# CLOCK.net
KiCad netlist of a schematic drawn in Altium Designer
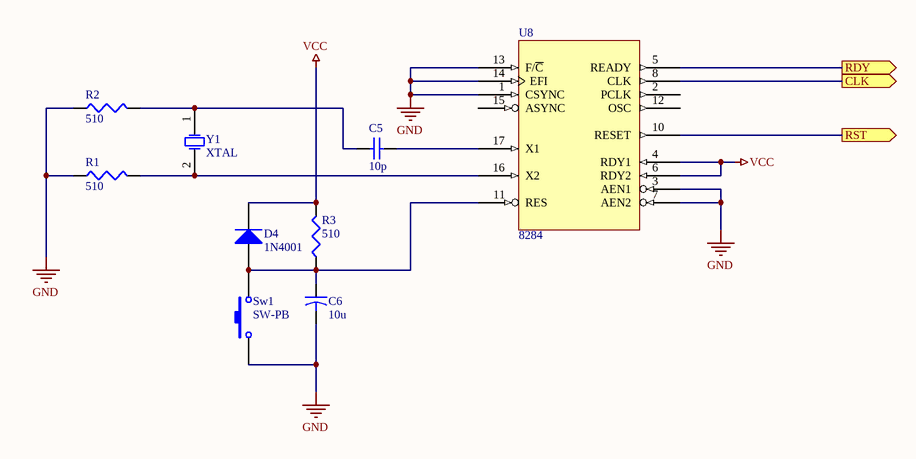
[diagram p0: CLOCK.SchDoc]

(export (version "E")
  (design (tool "Eeschema 10.0.6"))
  (components
    (comp (ref "C5")
      (value "10p")
      (footprint "RAD-0.3")
      (description "Capacitor")
      (fields (field (name "Comment") "Cap") (field (name "PUBLISHER") "Altium Limited"))
      (libsource (lib "8088") (part "Cap"))
    )
    (comp (ref "C6")
      (value "10u")
      (footprint "CAPR5-4X5")
      (description "Capacitor")
      (fields (field (name "Comment") "Cap2") (field (name "PUBLISHER") "Altium Limited"))
      (libsource (lib "8088") (part "Cap2"))
    )
    (comp (ref "D4")
      (value "1N4001")
      (footprint "DO-41")
      (description "1 Amp General Purpose Rectifier")
      (fields (field (name "PUBLISHER") "Altium Limited"))
      (libsource (lib "8088") (part "Diode 1N4001"))
    )
    (comp (ref "R1")
      (value "510")
      (footprint "J1-0603")
      (description "Resistor")
      (fields (field (name "Comment") "Res3") (field (name "PUBLISHER") "Altium Limited"))
      (libsource (lib "8088") (part "Res3"))
    )
    (comp (ref "R2")
      (value "510")
      (footprint "J1-0603")
      (description "Resistor")
      (fields (field (name "Comment") "Res3") (field (name "PUBLISHER") "Altium Limited"))
      (libsource (lib "8088") (part "Res3"))
    )
    (comp (ref "R3")
      (value "510")
      (footprint "J1-0603")
      (description "Resistor")
      (fields (field (name "Comment") "Res3") (field (name "PUBLISHER") "Altium Limited"))
      (libsource (lib "8088") (part "Res3"))
    )
    (comp (ref "Sw1")
      (value "SW-PB")
      (footprint "SPST-2")
      (description "Switch")
      (fields (field (name "PUBLISHER") "Altium Limited"))
      (libsource (lib "8088") (part "SW-PB"))
    )
    (comp (ref "U8") (value "8284") (footprint "DIP18") (libsource (lib "8088") (part "8284")))
    (comp (ref "Y1")
      (value "XTAL")
      (footprint "R38")
      (description "Crystal Oscillator")
      (fields (field (name "PUBLISHER") "Altium Limited"))
      (libsource (lib "8088") (part "XTAL"))
    )
  )
  (nets
    (net (code "1") (name "/CLK") (class "Default")
      (node (ref "U8") (pin "8") (pinfunction "CLK_8") (pintype "output"))
    )
    (net (code "2") (name "/RDY") (class "Default")
      (node (ref "U8") (pin "5") (pinfunction "READY_5") (pintype "output"))
    )
    (net (code "3") (name "/RST") (class "Default")
      (node (ref "U8") (pin "10") (pinfunction "RESET_10") (pintype "output"))
    )
    (net (code "4") (name "GND") (class "Default")
      (node (ref "C6") (pin "2") (pinfunction "2_2") (pintype "passive"))
      (node (ref "R1") (pin "1") (pinfunction "1_1") (pintype "passive"))
      (node (ref "R2") (pin "1") (pinfunction "1_1") (pintype "passive"))
      (node (ref "Sw1") (pin "1") (pinfunction "1_1") (pintype "passive"))
      (node (ref "U8") (pin "1") (pinfunction "CSYNC_1") (pintype "input"))
      (node (ref "U8") (pin "13") (pinfunction "F/~{C}_13") (pintype "input"))
      (node (ref "U8") (pin "14") (pinfunction "EFI_14") (pintype "input"))
      (node (ref "U8") (pin "3") (pinfunction "AEN1_3") (pintype "input"))
      (node (ref "U8") (pin "7") (pinfunction "AEN2_7") (pintype "input"))
      (node (ref "U8") (pin "9") (pinfunction "GND_9") (pintype "power_in"))
    )
    (net (code "5") (name "Net-(D4-A)") (class "Default")
      (node (ref "C6") (pin "1") (pinfunction "1_1") (pintype "passive"))
      (node (ref "D4") (pin "1") (pinfunction "A_1") (pintype "passive"))
      (node (ref "R3") (pin "1") (pinfunction "1_1") (pintype "passive"))
      (node (ref "Sw1") (pin "2") (pinfunction "2_2") (pintype "passive"))
      (node (ref "U8") (pin "11") (pinfunction "RES_11") (pintype "input"))
    )
    (net (code "6") (name "Net-(U8-X1)") (class "Default")
      (node (ref "C5") (pin "2") (pinfunction "2_2") (pintype "passive"))
      (node (ref "U8") (pin "17") (pinfunction "X1_17") (pintype "input"))
    )
    (net (code "7") (name "Net-(U8-X2)") (class "Default")
      (node (ref "R1") (pin "2") (pinfunction "2_2") (pintype "passive"))
      (node (ref "U8") (pin "16") (pinfunction "X2_16") (pintype "input"))
      (node (ref "Y1") (pin "2") (pinfunction "OSC2_2") (pintype "passive"))
    )
    (net (code "8") (name "Net-(Y1-OSC1)") (class "Default")
      (node (ref "C5") (pin "1") (pinfunction "1_1") (pintype "passive"))
      (node (ref "R2") (pin "2") (pinfunction "2_2") (pintype "passive"))
      (node (ref "Y1") (pin "1") (pinfunction "OSC1_1") (pintype "passive"))
    )
    (net (code "9") (name "VCC") (class "Default")
      (node (ref "D4") (pin "2") (pinfunction "K_2") (pintype "passive"))
      (node (ref "R3") (pin "2") (pinfunction "2_2") (pintype "passive"))
      (node (ref "U8") (pin "18") (pinfunction "VCC_18") (pintype "power_in"))
      (node (ref "U8") (pin "4") (pinfunction "RDY1_4") (pintype "input"))
      (node (ref "U8") (pin "6") (pinfunction "RDY2_6") (pintype "input"))
    )
    (net (code "10") (name "unconnected-(U8-ASYNC-Pad15)") (class "Default")
      (node (ref "U8") (pin "15") (pinfunction "ASYNC_15") (pintype "input"))
    )
    (net (code "11") (name "unconnected-(U8-OSC-Pad12)") (class "Default")
      (node (ref "U8") (pin "12") (pinfunction "OSC_12") (pintype "output"))
    )
    (net (code "12") (name "unconnected-(U8-PCLK-Pad2)") (class "Default")
      (node (ref "U8") (pin "2") (pinfunction "PCLK_2") (pintype "output"))
    )
  )
)
